# Analog-Mux-Breakout-v10.net
KiCad netlist of a schematic drawn in EAGLE
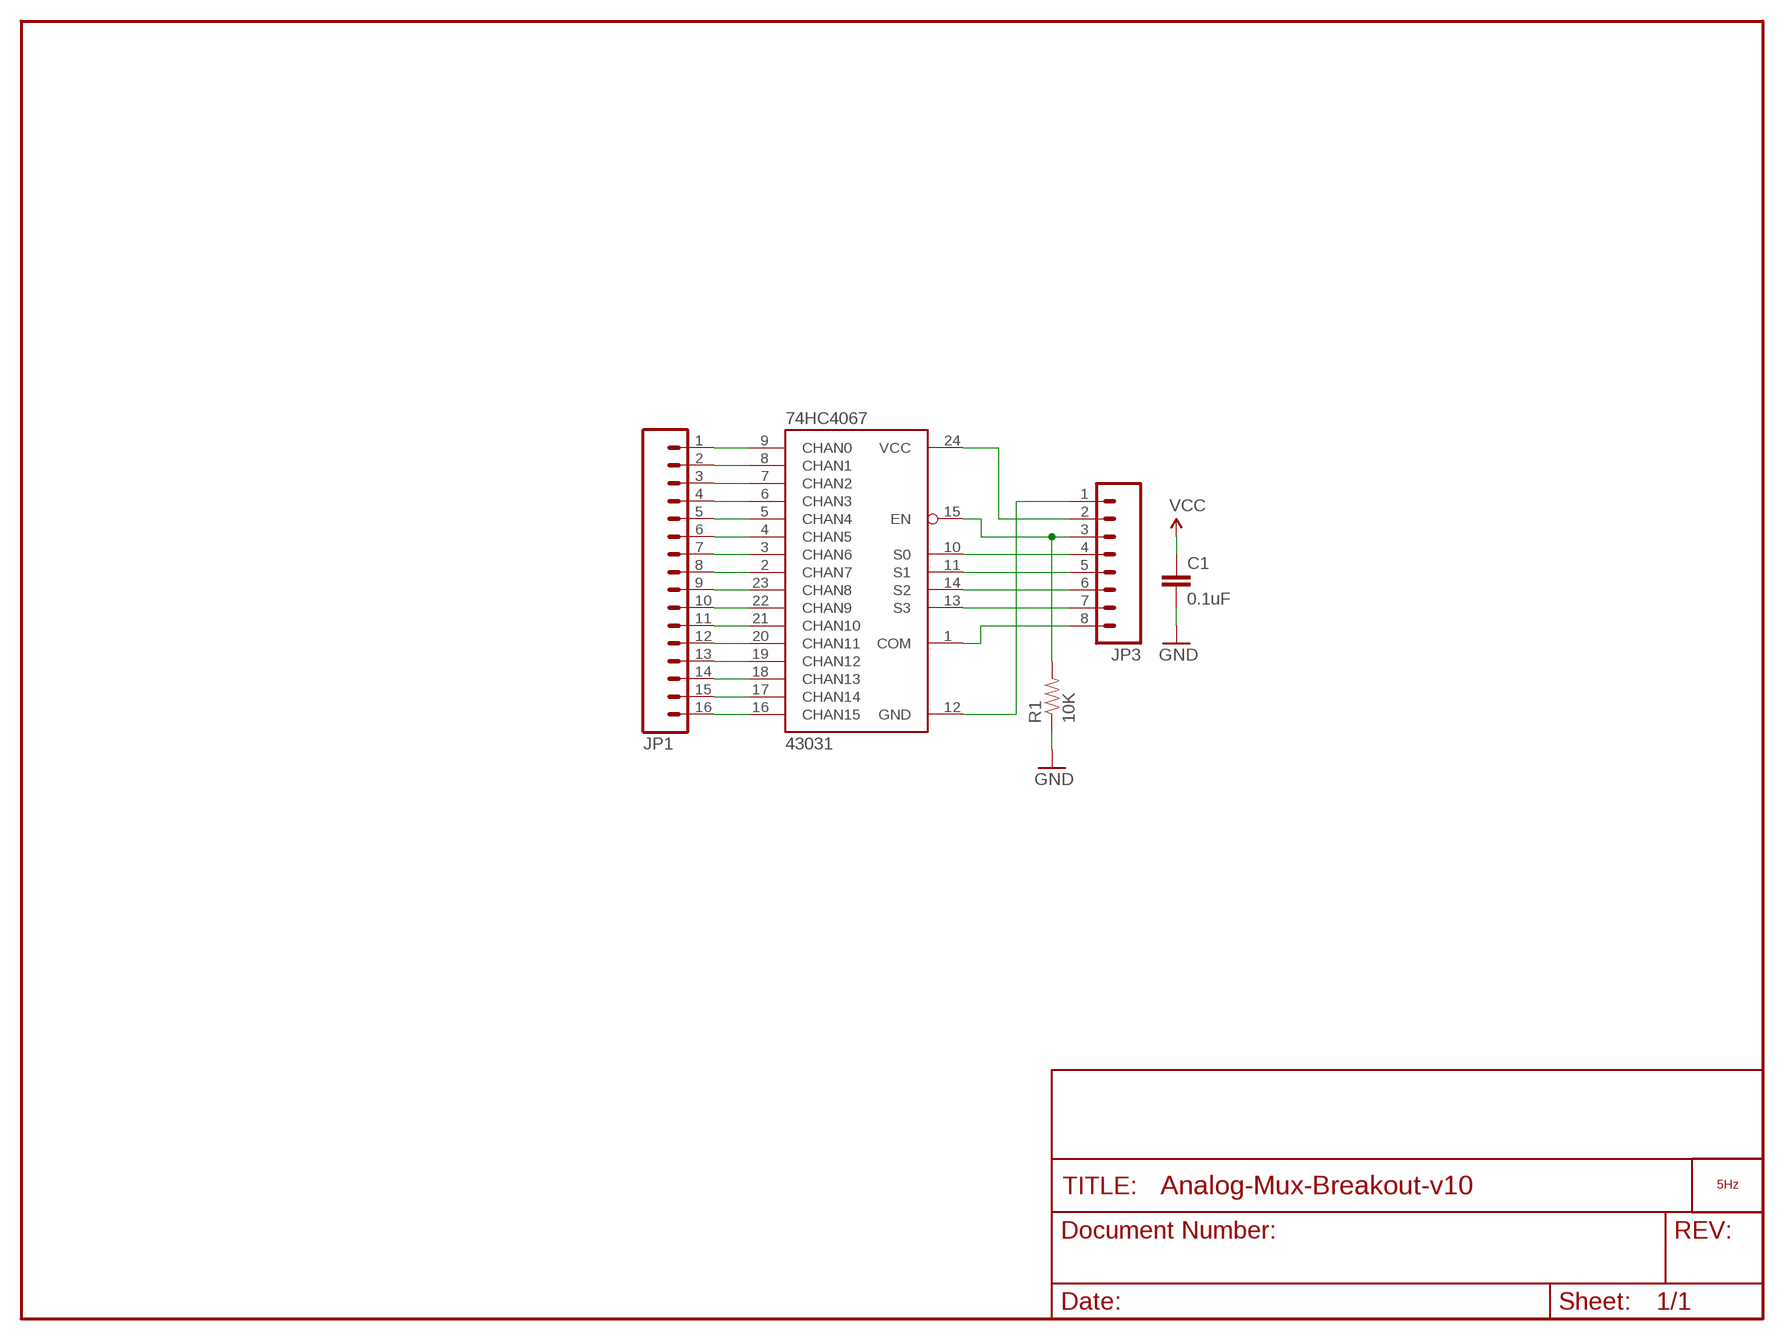
[diagram p0: schematic, sheet 1]

(export (version "E")
  (design (tool "Eeschema 10.0.6"))
  (components
    (comp (ref "74HC4067")
      (value "43031")
      (footprint "eagle-import:SSOP24")
      (libsource (lib "eagle-import") (part "MUX-74HC4067SMD"))
    )
    (comp (ref "C1")
      (value "0.1uF")
      (footprint "eagle-import:C0402")
      (libsource (lib "eagle-import") (part "CAP0402"))
    )
    (comp (ref "JP1")
      (value "M16PTH")
      (footprint "eagle-import:1X16")
      (libsource (lib "eagle-import") (part "M16PTH"))
    )
    (comp (ref "JP3")
      (value "M08")
      (footprint "eagle-import:1X08")
      (libsource (lib "eagle-import") (part "M08"))
    )
    (comp (ref "LOGO1")
      (value "LOGO_5HZ_H_10MM")
      (footprint "eagle-import:5HZ_LOGO_H_10MM")
      (libsource (lib "eagle-import") (part "LOGO_5HZ_H_10MM"))
    )
    (comp (ref "R1")
      (value "10K")
      (footprint "eagle-import:C0402")
      (libsource (lib "eagle-import") (part "RESISTOR0402"))
    )
  )
  (nets
    (net (code "1") (name "GND") (class "Default")
      (node (ref "74HC4067") (pin "12") (pinfunction "GND_12") (pintype "bidirectional"))
      (node (ref "C1") (pin "2") (pinfunction "2_2") (pintype "passive"))
      (node (ref "JP3") (pin "1") (pinfunction "1_1") (pintype "passive"))
      (node (ref "R1") (pin "1") (pinfunction "1_1") (pintype "passive"))
    )
    (net (code "2") (name "Net-(74HC4067-CHAN0)") (class "Default")
      (node (ref "74HC4067") (pin "9") (pinfunction "CHAN0_9") (pintype "bidirectional"))
      (node (ref "JP1") (pin "1") (pinfunction "1_1") (pintype "passive"))
    )
    (net (code "3") (name "Net-(74HC4067-CHAN1)") (class "Default")
      (node (ref "74HC4067") (pin "8") (pinfunction "CHAN1_8") (pintype "bidirectional"))
      (node (ref "JP1") (pin "2") (pinfunction "2_2") (pintype "passive"))
    )
    (net (code "4") (name "Net-(74HC4067-CHAN2)") (class "Default")
      (node (ref "74HC4067") (pin "7") (pinfunction "CHAN2_7") (pintype "bidirectional"))
      (node (ref "JP1") (pin "3") (pinfunction "3_3") (pintype "passive"))
    )
    (net (code "5") (name "Net-(74HC4067-CHAN3)") (class "Default")
      (node (ref "74HC4067") (pin "6") (pinfunction "CHAN3_6") (pintype "bidirectional"))
      (node (ref "JP1") (pin "4") (pinfunction "4_4") (pintype "passive"))
    )
    (net (code "6") (name "Net-(74HC4067-CHAN4)") (class "Default")
      (node (ref "74HC4067") (pin "5") (pinfunction "CHAN4_5") (pintype "bidirectional"))
      (node (ref "JP1") (pin "5") (pinfunction "5_5") (pintype "passive"))
    )
    (net (code "7") (name "Net-(74HC4067-CHAN5)") (class "Default")
      (node (ref "74HC4067") (pin "4") (pinfunction "CHAN5_4") (pintype "bidirectional"))
      (node (ref "JP1") (pin "6") (pinfunction "6_6") (pintype "passive"))
    )
    (net (code "8") (name "Net-(74HC4067-CHAN6)") (class "Default")
      (node (ref "74HC4067") (pin "3") (pinfunction "CHAN6_3") (pintype "bidirectional"))
      (node (ref "JP1") (pin "7") (pinfunction "7_7") (pintype "passive"))
    )
    (net (code "9") (name "Net-(74HC4067-CHAN7)") (class "Default")
      (node (ref "74HC4067") (pin "2") (pinfunction "CHAN7_2") (pintype "bidirectional"))
      (node (ref "JP1") (pin "8") (pinfunction "8_8") (pintype "passive"))
    )
    (net (code "10") (name "Net-(74HC4067-CHAN8)") (class "Default")
      (node (ref "74HC4067") (pin "23") (pinfunction "CHAN8_23") (pintype "bidirectional"))
      (node (ref "JP1") (pin "9") (pinfunction "9_9") (pintype "passive"))
    )
    (net (code "11") (name "Net-(74HC4067-CHAN9)") (class "Default")
      (node (ref "74HC4067") (pin "22") (pinfunction "CHAN9_22") (pintype "bidirectional"))
      (node (ref "JP1") (pin "10") (pinfunction "10_10") (pintype "passive"))
    )
    (net (code "12") (name "Net-(74HC4067-CHAN10)") (class "Default")
      (node (ref "74HC4067") (pin "21") (pinfunction "CHAN10_21") (pintype "bidirectional"))
      (node (ref "JP1") (pin "11") (pinfunction "11_11") (pintype "passive"))
    )
    (net (code "13") (name "Net-(74HC4067-CHAN11)") (class "Default")
      (node (ref "74HC4067") (pin "20") (pinfunction "CHAN11_20") (pintype "bidirectional"))
      (node (ref "JP1") (pin "12") (pinfunction "12_12") (pintype "passive"))
    )
    (net (code "14") (name "Net-(74HC4067-CHAN12)") (class "Default")
      (node (ref "74HC4067") (pin "19") (pinfunction "CHAN12_19") (pintype "bidirectional"))
      (node (ref "JP1") (pin "13") (pinfunction "13_13") (pintype "passive"))
    )
    (net (code "15") (name "Net-(74HC4067-CHAN13)") (class "Default")
      (node (ref "74HC4067") (pin "18") (pinfunction "CHAN13_18") (pintype "bidirectional"))
      (node (ref "JP1") (pin "14") (pinfunction "14_14") (pintype "passive"))
    )
    (net (code "16") (name "Net-(74HC4067-CHAN14)") (class "Default")
      (node (ref "74HC4067") (pin "17") (pinfunction "CHAN14_17") (pintype "bidirectional"))
      (node (ref "JP1") (pin "15") (pinfunction "15_15") (pintype "passive"))
    )
    (net (code "17") (name "Net-(74HC4067-CHAN15)") (class "Default")
      (node (ref "74HC4067") (pin "16") (pinfunction "CHAN15_16") (pintype "bidirectional"))
      (node (ref "JP1") (pin "16") (pinfunction "16_16") (pintype "passive"))
    )
    (net (code "18") (name "Net-(74HC4067-COM)") (class "Default")
      (node (ref "74HC4067") (pin "1") (pinfunction "COM_1") (pintype "bidirectional"))
      (node (ref "JP3") (pin "8") (pinfunction "8_8") (pintype "passive"))
    )
    (net (code "19") (name "Net-(74HC4067-EN)") (class "Default")
      (node (ref "74HC4067") (pin "15") (pinfunction "EN_15") (pintype "input"))
      (node (ref "JP3") (pin "3") (pinfunction "3_3") (pintype "passive"))
      (node (ref "R1") (pin "2") (pinfunction "2_2") (pintype "passive"))
    )
    (net (code "20") (name "Net-(74HC4067-S0)") (class "Default")
      (node (ref "74HC4067") (pin "10") (pinfunction "S0_10") (pintype "input"))
      (node (ref "JP3") (pin "4") (pinfunction "4_4") (pintype "passive"))
    )
    (net (code "21") (name "Net-(74HC4067-S1)") (class "Default")
      (node (ref "74HC4067") (pin "11") (pinfunction "S1_11") (pintype "input"))
      (node (ref "JP3") (pin "5") (pinfunction "5_5") (pintype "passive"))
    )
    (net (code "22") (name "Net-(74HC4067-S2)") (class "Default")
      (node (ref "74HC4067") (pin "14") (pinfunction "S2_14") (pintype "input"))
      (node (ref "JP3") (pin "6") (pinfunction "6_6") (pintype "passive"))
    )
    (net (code "23") (name "Net-(74HC4067-S3)") (class "Default")
      (node (ref "74HC4067") (pin "13") (pinfunction "S3_13") (pintype "input"))
      (node (ref "JP3") (pin "7") (pinfunction "7_7") (pintype "passive"))
    )
    (net (code "24") (name "VCC") (class "Default")
      (node (ref "74HC4067") (pin "24") (pinfunction "VCC_24") (pintype "bidirectional"))
      (node (ref "C1") (pin "1") (pinfunction "1_1") (pintype "passive"))
      (node (ref "JP3") (pin "2") (pinfunction "2_2") (pintype "passive"))
    )
  )
)
